# CH32L103G8R-R0.net
KiCad netlist of a schematic drawn in Altium Designer
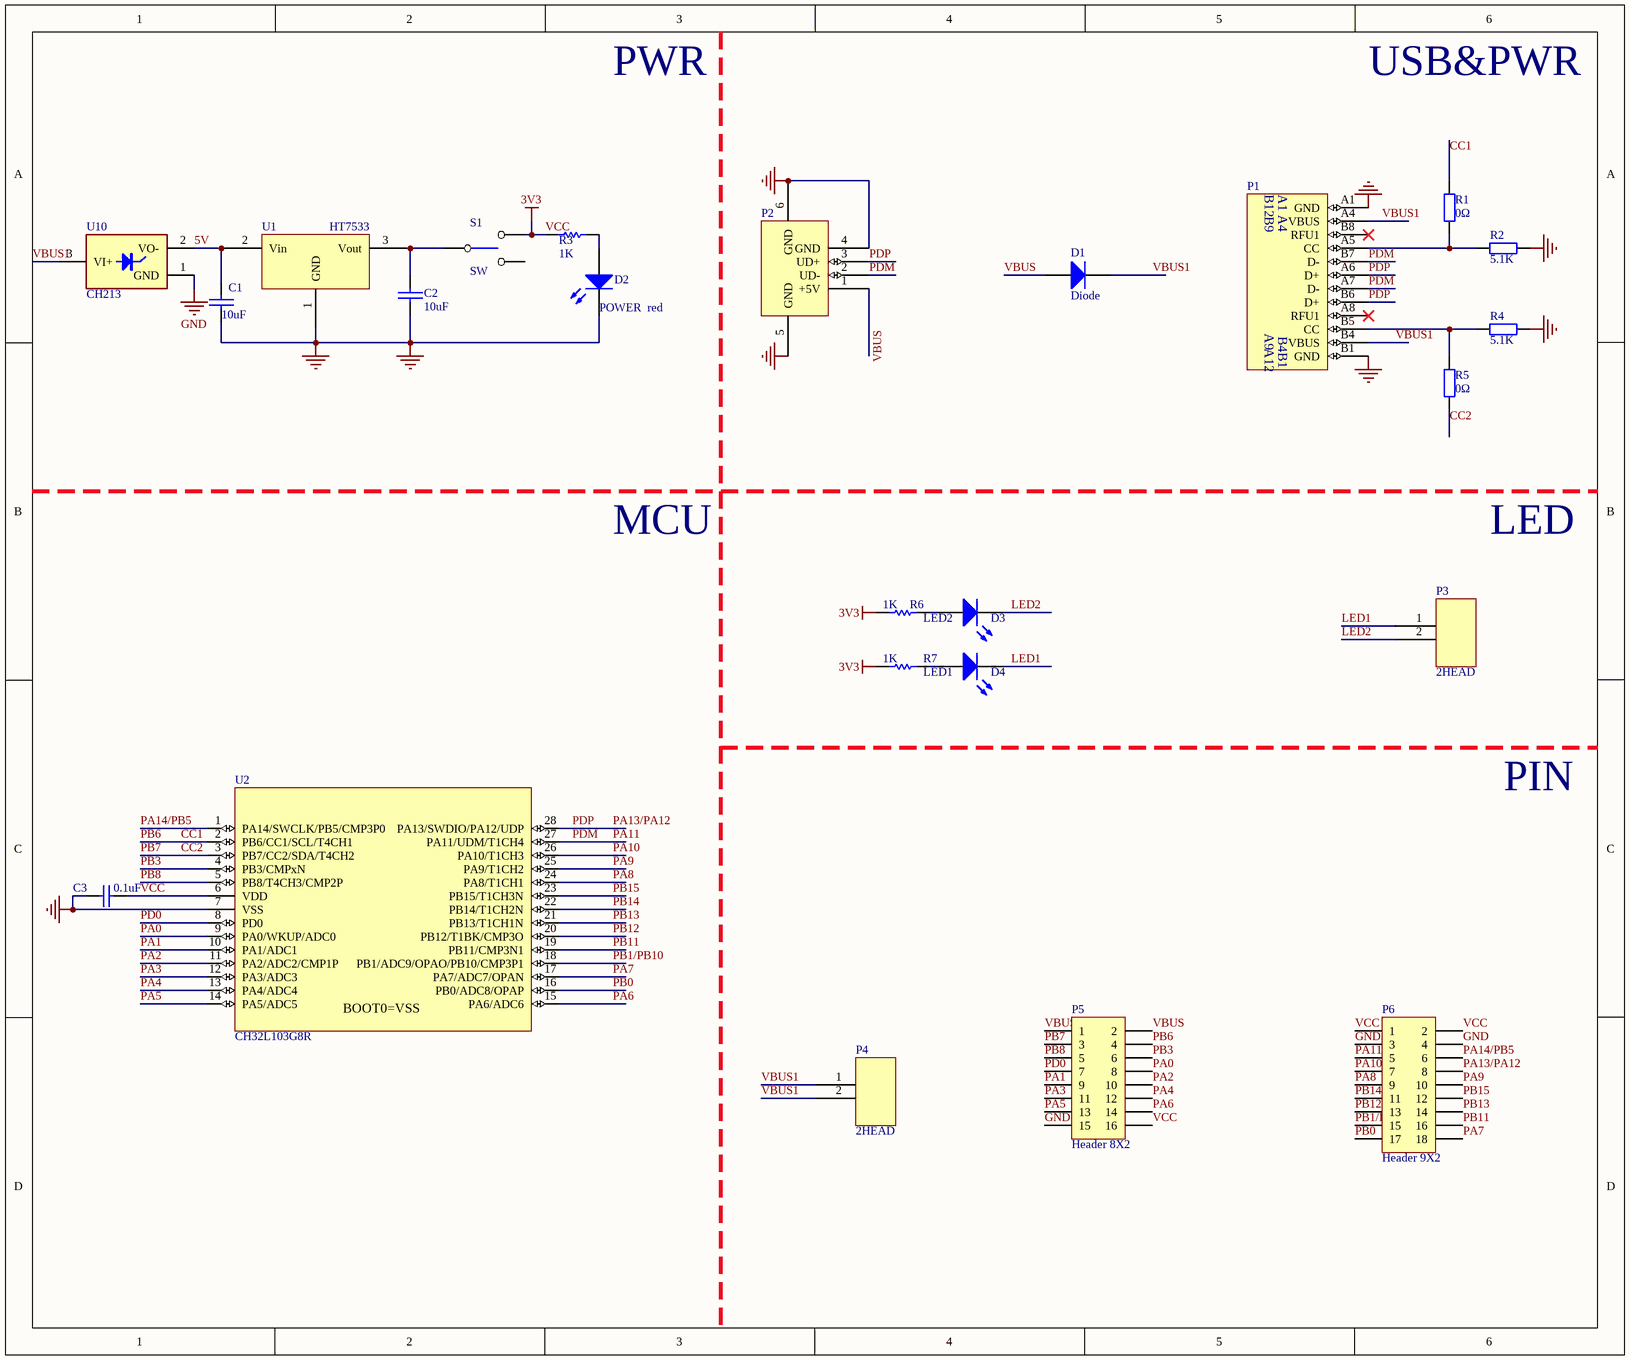
[diagram p0: CH32L103G8R-R0.SchDoc]

(export (version "E")
  (design (tool "Eeschema 10.0.6"))
  (components
    (comp (ref "C1")
      (value "10uF")
      (footprint "0603_C")
      (description "Capacitor")
      (libsource (lib "*") (part "CAP"))
    )
    (comp (ref "C2")
      (value "10uF")
      (footprint "0603_C")
      (description "Capacitor")
      (libsource (lib "*") (part "CAP"))
    )
    (comp (ref "C3")
      (value "0.1uF")
      (footprint "0603_C")
      (description "Capacitor")
      (fields (field (name "PUBLISHER") "Altium Limited"))
      (libsource (lib "*") (part "Cap"))
    )
    (comp (ref "D1")
      (value "Diode")
      (footprint "SOD-123")
      (description "Default Diode")
      (fields (field (name "PUBLISHER") "Altium Limited"))
      (libsource (lib "Miscellaneous Devices") (part "Diode"))
    )
    (comp (ref "D2")
      (value "POWER  red")
      (footprint "0603+")
      (description "Typical INFRARED GaAs LED")
      (fields (field (name "PUBLISHER") "Altium Limited"))
      (libsource (lib "*") (part "LED0"))
    )
    (comp (ref "D3")
      (value "LED2")
      (footprint "0603+")
      (description "Typical INFRARED GaAs LED")
      (fields (field (name "PUBLISHER") "Altium Limited"))
      (libsource (lib "*") (part "LED0"))
    )
    (comp (ref "D4")
      (value "LED1")
      (footprint "0603+")
      (description "Typical INFRARED GaAs LED")
      (fields (field (name "PUBLISHER") "Altium Limited"))
      (libsource (lib "*") (part "LED0"))
    )
    (comp (ref "P1")
      (value "TYPE-C")
      (footprint "TYPE-C-Receptacle-2.0")
      (libsource (lib "*") (part "TYPE-C1"))
    )
    (comp (ref "P2")
      (value "USB_A")
      (footprint "USBAF")
      (description "USB Port")
      (libsource (lib "*") (part "USB"))
    )
    (comp (ref "P3") (value "2HEAD") (footprint "SIP2-2.54mm") (libsource (lib "*") (part "2HEAD")))
    (comp (ref "P4") (value "2HEAD") (footprint "SIP2-2.54mm") (libsource (lib "*") (part "2HEAD")))
    (comp (ref "P5")
      (value "Header 8X2")
      (footprint "HDR2X8")
      (description "Header, 8-Pin, Dual row")
      (fields (field (name "PUBLISHER") "Altium Limited"))
      (libsource (lib "Miscellaneous Connectors") (part "Header 8X2"))
    )
    (comp (ref "P6")
      (value "Header 9X2")
      (footprint "HDR2X9")
      (description "Header, 9-Pin, Dual row")
      (fields (field (name "PUBLISHER") "Altium Limited"))
      (libsource (lib "Miscellaneous Connectors") (part "Header 9X2"))
    )
    (comp (ref "R1")
      (value "0Ω")
      (footprint "0603")
      (description "Resistor")
      (libsource (lib "") (part "Res2_1"))
    )
    (comp (ref "R2")
      (value "5.1K")
      (footprint "0603")
      (description "Resistor")
      (libsource (lib "Miscellaneous Devices") (part "Res2"))
    )
    (comp (ref "R3")
      (value "1K")
      (footprint "0603")
      (description "Semiconductor Resistor")
      (libsource (lib "*") (part "Res Semi"))
    )
    (comp (ref "R4")
      (value "5.1K")
      (footprint "0603")
      (description "Resistor")
      (libsource (lib "Miscellaneous Devices") (part "Res2"))
    )
    (comp (ref "R5")
      (value "0Ω")
      (footprint "0603")
      (description "Resistor")
      (libsource (lib "") (part "Res2_1"))
    )
    (comp (ref "R6")
      (value "1K")
      (footprint "0603")
      (description "Semiconductor Resistor")
      (libsource (lib "*") (part "Res Semi"))
    )
    (comp (ref "R7")
      (value "1K")
      (footprint "0603")
      (description "Semiconductor Resistor")
      (libsource (lib "*") (part "Res Semi"))
    )
    (comp (ref "S1") (value "SW") (footprint "SW1") (libsource (lib "*") (part "SW")))
    (comp (ref "U1")
      (value "HT7533")
      (footprint "SOT-89")
      (libsource (lib "wch_sch_others") (part "1117-3.3V"))
    )
    (comp (ref "U2")
      (value "CH32L103G8R")
      (footprint "QSOP28")
      (description "RISC-V LMD-MCU, 96MHz, USB, Type-C, CAN, OPA, lower power")
      (libsource (lib "CHXXX") (part "CH32L103G8R"))
    )
    (comp (ref "U10")
      (value "CH213")
      (footprint "SOT-23-3")
      (description "Ideal Diode 5V*1A")
      (libsource (lib "CHXXX") (part "CH213E"))
    )
  )
  (nets
    (net (code "1") (name "/5V") (class "Default")
      (node (ref "C1") (pin "1") (pinfunction "1_1") (pintype "passive"))
      (node (ref "U1") (pin "2") (pinfunction "Vin_2") (pintype "passive"))
      (node (ref "U10") (pin "2") (pinfunction "VO-_2") (pintype "power_in"))
    )
    (net (code "3") (name "/CC1") (class "Default")
      (node (ref "P5") (pin "4") (pinfunction "4_4") (pintype "passive"))
      (node (ref "R1") (pin "2") (pinfunction "2_2") (pintype "passive"))
      (node (ref "U2") (pin "2") (pinfunction "PB6/CC1/SCL/T4CH1_2") (pintype "bidirectional"))
    )
    (net (code "4") (name "/CC2") (class "Default")
      (node (ref "P5") (pin "3") (pinfunction "3_3") (pintype "passive"))
      (node (ref "R5") (pin "1") (pinfunction "1_1") (pintype "passive"))
      (node (ref "U2") (pin "3") (pinfunction "PB7/CC2/SDA/T4CH2_3") (pintype "bidirectional"))
    )
    (net (code "5") (name "/LED1") (class "Default")
      (node (ref "D4") (pin "2") (pinfunction "K_2") (pintype "passive"))
      (node (ref "P3") (pin "1") (pintype "passive"))
    )
    (net (code "6") (name "/LED2") (class "Default")
      (node (ref "D3") (pin "2") (pinfunction "K_2") (pintype "passive"))
      (node (ref "P3") (pin "2") (pintype "passive"))
    )
    (net (code "7") (name "/PA0") (class "Default")
      (node (ref "P5") (pin "8") (pinfunction "8_8") (pintype "passive"))
      (node (ref "U2") (pin "9") (pinfunction "PA0/WKUP/ADC0_9") (pintype "bidirectional"))
    )
    (net (code "8") (name "/PA1") (class "Default")
      (node (ref "P5") (pin "9") (pinfunction "9_9") (pintype "passive"))
      (node (ref "U2") (pin "10") (pinfunction "PA1/ADC1_10") (pintype "bidirectional"))
    )
    (net (code "9") (name "/PA2") (class "Default")
      (node (ref "P5") (pin "10") (pinfunction "10_10") (pintype "passive"))
      (node (ref "U2") (pin "11") (pinfunction "PA2/ADC2/CMP1P_11") (pintype "bidirectional"))
    )
    (net (code "10") (name "/PA3") (class "Default")
      (node (ref "P5") (pin "11") (pinfunction "11_11") (pintype "passive"))
      (node (ref "U2") (pin "12") (pinfunction "PA3/ADC3_12") (pintype "bidirectional"))
    )
    (net (code "11") (name "/PA4") (class "Default")
      (node (ref "P5") (pin "12") (pinfunction "12_12") (pintype "passive"))
      (node (ref "U2") (pin "13") (pinfunction "PA4/ADC4_13") (pintype "bidirectional"))
    )
    (net (code "12") (name "/PA5") (class "Default")
      (node (ref "P5") (pin "13") (pinfunction "13_13") (pintype "passive"))
      (node (ref "U2") (pin "14") (pinfunction "PA5/ADC5_14") (pintype "bidirectional"))
    )
    (net (code "13") (name "/PA6") (class "Default")
      (node (ref "P5") (pin "14") (pinfunction "14_14") (pintype "passive"))
      (node (ref "U2") (pin "15") (pinfunction "PA6/ADC6_15") (pintype "bidirectional"))
    )
    (net (code "14") (name "/PA7") (class "Default")
      (node (ref "P6") (pin "18") (pinfunction "18_18") (pintype "passive"))
      (node (ref "U2") (pin "17") (pinfunction "PA7/ADC7/OPAN_17") (pintype "bidirectional"))
    )
    (net (code "15") (name "/PA8") (class "Default")
      (node (ref "P6") (pin "9") (pinfunction "9_9") (pintype "passive"))
      (node (ref "U2") (pin "24") (pinfunction "PA8/T1CH1_24") (pintype "bidirectional"))
    )
    (net (code "16") (name "/PA9") (class "Default")
      (node (ref "P6") (pin "10") (pinfunction "10_10") (pintype "passive"))
      (node (ref "U2") (pin "25") (pinfunction "PA9/T1CH2_25") (pintype "bidirectional"))
    )
    (net (code "17") (name "/PA10") (class "Default")
      (node (ref "P6") (pin "7") (pinfunction "7_7") (pintype "passive"))
      (node (ref "U2") (pin "26") (pinfunction "PA10/T1CH3_26") (pintype "bidirectional"))
    )
    (net (code "18") (name "/PA11") (class "Default")
      (node (ref "P1") (pin "A7") (pinfunction "D-_A7") (pintype "bidirectional"))
      (node (ref "P1") (pin "B7") (pinfunction "D-_B7") (pintype "bidirectional"))
      (node (ref "P2") (pin "2") (pinfunction "UD-_2") (pintype "bidirectional"))
      (node (ref "P6") (pin "5") (pinfunction "5_5") (pintype "passive"))
      (node (ref "U2") (pin "27") (pinfunction "PA11/UDM/T1CH4_27") (pintype "bidirectional"))
    )
    (net (code "19") (name "/PA13{slash}PA12") (class "Default")
      (node (ref "P1") (pin "A6") (pinfunction "D+_A6") (pintype "bidirectional"))
      (node (ref "P1") (pin "B6") (pinfunction "D+_B6") (pintype "bidirectional"))
      (node (ref "P2") (pin "3") (pinfunction "UD+_3") (pintype "bidirectional"))
      (node (ref "P6") (pin "8") (pinfunction "8_8") (pintype "passive"))
      (node (ref "U2") (pin "28") (pinfunction "PA13/SWDIO/PA12/UDP_28") (pintype "bidirectional"))
    )
    (net (code "20") (name "/PA14{slash}PB5") (class "Default")
      (node (ref "P6") (pin "6") (pinfunction "6_6") (pintype "passive"))
      (node (ref "U2") (pin "1") (pinfunction "PA14/SWCLK/PB5/CMP3P0_1") (pintype "bidirectional"))
    )
    (net (code "21") (name "/PB0") (class "Default")
      (node (ref "P6") (pin "17") (pinfunction "17_17") (pintype "passive"))
      (node (ref "U2") (pin "16") (pinfunction "PB0/ADC8/OPAP_16") (pintype "bidirectional"))
    )
    (net (code "22") (name "/PB1{slash}PB10") (class "Default")
      (node (ref "P6") (pin "15") (pinfunction "15_15") (pintype "passive"))
      (node (ref "U2") (pin "18") (pinfunction "PB1/ADC9/OPAO/PB10/CMP3P1_18") (pintype "bidirectional"))
    )
    (net (code "23") (name "/PB3") (class "Default")
      (node (ref "P5") (pin "6") (pinfunction "6_6") (pintype "passive"))
      (node (ref "U2") (pin "4") (pinfunction "PB3/CMPxN_4") (pintype "bidirectional"))
    )
    (net (code "24") (name "/PB8") (class "Default")
      (node (ref "P5") (pin "5") (pinfunction "5_5") (pintype "passive"))
      (node (ref "U2") (pin "5") (pinfunction "PB8/T4CH3/CMP2P_5") (pintype "bidirectional"))
    )
    (net (code "25") (name "/PB11") (class "Default")
      (node (ref "P6") (pin "16") (pinfunction "16_16") (pintype "passive"))
      (node (ref "U2") (pin "19") (pinfunction "PB11/CMP3N1_19") (pintype "bidirectional"))
    )
    (net (code "26") (name "/PB12") (class "Default")
      (node (ref "P6") (pin "13") (pinfunction "13_13") (pintype "passive"))
      (node (ref "U2") (pin "20") (pinfunction "PB12/T1BK/CMP3O_20") (pintype "bidirectional"))
    )
    (net (code "27") (name "/PB13") (class "Default")
      (node (ref "P6") (pin "14") (pinfunction "14_14") (pintype "passive"))
      (node (ref "U2") (pin "21") (pinfunction "PB13/T1CH1N_21") (pintype "bidirectional"))
    )
    (net (code "28") (name "/PB14") (class "Default")
      (node (ref "P6") (pin "11") (pinfunction "11_11") (pintype "passive"))
      (node (ref "U2") (pin "22") (pinfunction "PB14/T1CH2N_22") (pintype "bidirectional"))
    )
    (net (code "29") (name "/PB15") (class "Default")
      (node (ref "P6") (pin "12") (pinfunction "12_12") (pintype "passive"))
      (node (ref "U2") (pin "23") (pinfunction "PB15/T1CH3N_23") (pintype "bidirectional"))
    )
    (net (code "30") (name "/PD0") (class "Default")
      (node (ref "P5") (pin "7") (pinfunction "7_7") (pintype "passive"))
      (node (ref "U2") (pin "8") (pinfunction "PD0_8") (pintype "bidirectional"))
    )
    (net (code "31") (name "/VBUS") (class "Default")
      (node (ref "D1") (pin "1") (pinfunction "A_1") (pintype "passive"))
      (node (ref "P2") (pin "1") (pinfunction "+5V_1") (pintype "power_in"))
      (node (ref "P5") (pin "1") (pinfunction "1_1") (pintype "passive"))
      (node (ref "P5") (pin "2") (pinfunction "2_2") (pintype "passive"))
    )
    (net (code "32") (name "/VBUS1") (class "Default")
      (node (ref "D1") (pin "2") (pinfunction "K_2") (pintype "passive"))
      (node (ref "P1") (pin "A4") (pinfunction "VBUS_A4") (pintype "bidirectional"))
      (node (ref "P1") (pin "B4") (pinfunction "VBUS_B4") (pintype "bidirectional"))
      (node (ref "P4") (pin "1") (pintype "passive"))
      (node (ref "P4") (pin "2") (pintype "passive"))
      (node (ref "U10") (pin "3") (pinfunction "VI+_3") (pintype "power_in"))
    )
    (net (code "33") (name "3V3") (class "Default")
      (node (ref "C3") (pin "1") (pinfunction "1_1") (pintype "passive"))
      (node (ref "P5") (pin "16") (pinfunction "16_16") (pintype "passive"))
      (node (ref "P6") (pin "1") (pinfunction "1_1") (pintype "passive"))
      (node (ref "P6") (pin "2") (pinfunction "2_2") (pintype "passive"))
      (node (ref "R3") (pin "2") (pinfunction "2_2") (pintype "passive"))
      (node (ref "R6") (pin "1") (pinfunction "1_1") (pintype "passive"))
      (node (ref "R7") (pin "1") (pinfunction "1_1") (pintype "passive"))
      (node (ref "S1") (pin "3") (pinfunction "3_3") (pintype "passive"))
      (node (ref "U2") (pin "6") (pinfunction "VDD_6") (pintype "power_in"))
    )
    (net (code "34") (name "GND") (class "Default")
      (node (ref "C1") (pin "2") (pinfunction "2_2") (pintype "passive"))
      (node (ref "C2") (pin "2") (pinfunction "2_2") (pintype "passive"))
      (node (ref "C3") (pin "2") (pinfunction "2_2") (pintype "passive"))
      (node (ref "D2") (pin "2") (pinfunction "K_2") (pintype "passive"))
      (node (ref "P1") (pin "A1") (pinfunction "GND_A1") (pintype "bidirectional"))
      (node (ref "P1") (pin "B1") (pinfunction "GND_B1") (pintype "bidirectional"))
      (node (ref "P2") (pin "4") (pinfunction "GND_4") (pintype "power_in"))
      (node (ref "P2") (pin "5") (pinfunction "GND_5") (pintype "power_in"))
      (node (ref "P2") (pin "6") (pinfunction "GND_6") (pintype "power_in"))
      (node (ref "P5") (pin "15") (pinfunction "15_15") (pintype "passive"))
      (node (ref "P6") (pin "3") (pinfunction "3_3") (pintype "passive"))
      (node (ref "P6") (pin "4") (pinfunction "4_4") (pintype "passive"))
      (node (ref "R2") (pin "2") (pinfunction "2_2") (pintype "passive"))
      (node (ref "R4") (pin "2") (pinfunction "2_2") (pintype "passive"))
      (node (ref "U1") (pin "1") (pinfunction "GND_1") (pintype "passive"))
      (node (ref "U10") (pin "1") (pinfunction "GND_1") (pintype "power_in"))
      (node (ref "U2") (pin "7") (pinfunction "VSS_7") (pintype "power_in"))
    )
    (net (code "35") (name "Net-(D2-A)") (class "Default")
      (node (ref "D2") (pin "1") (pinfunction "A_1") (pintype "passive"))
      (node (ref "R3") (pin "1") (pinfunction "1_1") (pintype "passive"))
    )
    (net (code "36") (name "Net-(D3-A)") (class "Default")
      (node (ref "D3") (pin "1") (pinfunction "A_1") (pintype "passive"))
      (node (ref "R6") (pin "2") (pinfunction "2_2") (pintype "passive"))
    )
    (net (code "37") (name "Net-(D4-A)") (class "Default")
      (node (ref "D4") (pin "1") (pinfunction "A_1") (pintype "passive"))
      (node (ref "R7") (pin "2") (pinfunction "2_2") (pintype "passive"))
    )
    (net (code "38") (name "Net-(P1-CC-PadA5)") (class "Default")
      (node (ref "P1") (pin "A5") (pinfunction "CC_A5") (pintype "bidirectional"))
      (node (ref "R1") (pin "1") (pinfunction "1_1") (pintype "passive"))
      (node (ref "R2") (pin "1") (pinfunction "1_1") (pintype "passive"))
    )
    (net (code "39") (name "Net-(P1-CC-PadB5)") (class "Default")
      (node (ref "P1") (pin "B5") (pinfunction "CC_B5") (pintype "bidirectional"))
      (node (ref "R4") (pin "1") (pinfunction "1_1") (pintype "passive"))
      (node (ref "R5") (pin "2") (pinfunction "2_2") (pintype "passive"))
    )
    (net (code "40") (name "Net-(U1-Vout)") (class "Default")
      (node (ref "C2") (pin "1") (pinfunction "1_1") (pintype "passive"))
      (node (ref "S1") (pin "1") (pinfunction "1_1") (pintype "passive"))
      (node (ref "U1") (pin "3") (pinfunction "Vout_3") (pintype "passive"))
    )
    (net (code "41") (name "unconnected-(P1-RFU1-PadA8)") (class "Default")
      (node (ref "P1") (pin "A8") (pinfunction "RFU1_A8") (pintype "bidirectional+no_connect"))
    )
    (net (code "42") (name "unconnected-(P1-RFU1-PadB8)") (class "Default")
      (node (ref "P1") (pin "B8") (pinfunction "RFU1_B8") (pintype "bidirectional+no_connect"))
    )
    (net (code "43") (name "unconnected-(S1-Pad2)") (class "Default")
      (node (ref "S1") (pin "2") (pinfunction "2_2") (pintype "passive"))
    )
  )
)
